# Arduino_shield.net
KiCad netlist of a schematic drawn in EAGLE
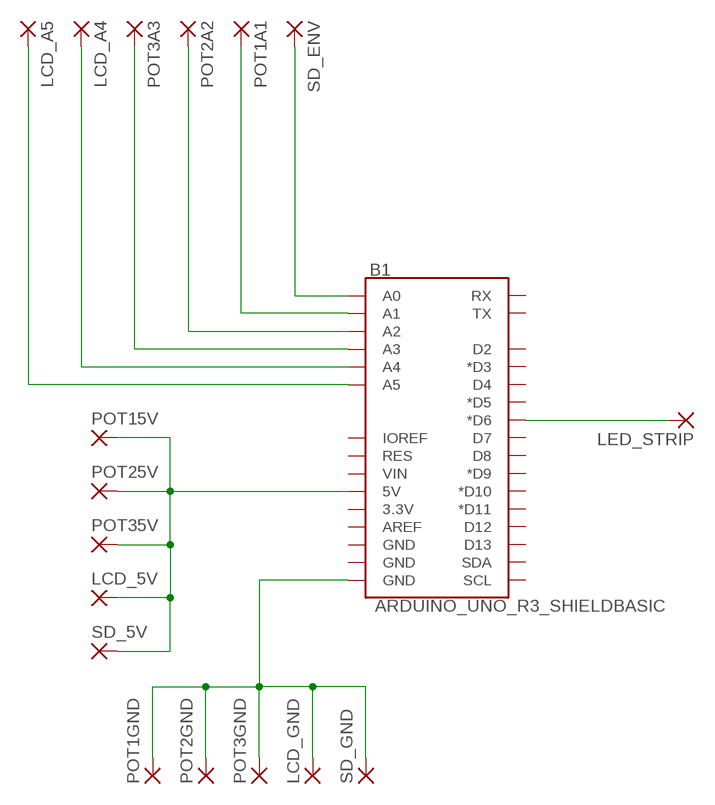
[diagram p0: schematic, sheet 1]

(export (version "E")
  (design (tool "Eeschema 10.0.6"))
  (components
    (comp (ref "B1")
      (value "ARDUINO_UNO_R3_SHIELDBASIC")
      (footprint "eagle-import:UNO_R3_SHIELD")
      (libsource (lib "eagle-import") (part "ARDUINO_UNO_R3_SHIELDBASIC"))
    )
    (comp (ref "LCD_5V")
      (value "1,6/0,9")
      (footprint "eagle-import:1,6_0,9")
      (libsource (lib "eagle-import") (part "1,6/0,9"))
    )
    (comp (ref "LCD_A4")
      (value "1,6/0,9")
      (footprint "eagle-import:1,6_0,9")
      (libsource (lib "eagle-import") (part "1,6/0,9"))
    )
    (comp (ref "LCD_A5")
      (value "1,6/0,9")
      (footprint "eagle-import:1,6_0,9")
      (libsource (lib "eagle-import") (part "1,6/0,9"))
    )
    (comp (ref "LCD_GND")
      (value "1,6/0,9")
      (footprint "eagle-import:1,6_0,9")
      (libsource (lib "eagle-import") (part "1,6/0,9"))
    )
    (comp (ref "LED_STRIP")
      (value "1,6/0,9")
      (footprint "eagle-import:1,6_0,9")
      (libsource (lib "eagle-import") (part "1,6/0,9"))
    )
    (comp (ref "POT1A1")
      (value "1,6/0,9")
      (footprint "eagle-import:1,6_0,9")
      (libsource (lib "eagle-import") (part "1,6/0,9"))
    )
    (comp (ref "POT1GND")
      (value "1,6/0,9")
      (footprint "eagle-import:1,6_0,9")
      (libsource (lib "eagle-import") (part "1,6/0,9"))
    )
    (comp (ref "POT2A2")
      (value "1,6/0,9")
      (footprint "eagle-import:1,6_0,9")
      (libsource (lib "eagle-import") (part "1,6/0,9"))
    )
    (comp (ref "POT2GND")
      (value "1,6/0,9")
      (footprint "eagle-import:1,6_0,9")
      (libsource (lib "eagle-import") (part "1,6/0,9"))
    )
    (comp (ref "POT3A3")
      (value "1,6/0,9")
      (footprint "eagle-import:1,6_0,9")
      (libsource (lib "eagle-import") (part "1,6/0,9"))
    )
    (comp (ref "POT3GND")
      (value "1,6/0,9")
      (footprint "eagle-import:1,6_0,9")
      (libsource (lib "eagle-import") (part "1,6/0,9"))
    )
    (comp (ref "POT15V")
      (value "1,6/0,9")
      (footprint "eagle-import:1,6_0,9")
      (libsource (lib "eagle-import") (part "1,6/0,9"))
    )
    (comp (ref "POT25V")
      (value "1,6/0,9")
      (footprint "eagle-import:1,6_0,9")
      (libsource (lib "eagle-import") (part "1,6/0,9"))
    )
    (comp (ref "POT35V")
      (value "1,6/0,9")
      (footprint "eagle-import:1,6_0,9")
      (libsource (lib "eagle-import") (part "1,6/0,9"))
    )
    (comp (ref "SD_5V")
      (value "1,6/0,9")
      (footprint "eagle-import:1,6_0,9")
      (libsource (lib "eagle-import") (part "1,6/0,9"))
    )
    (comp (ref "SD_ENV")
      (value "1,6/0,9")
      (footprint "eagle-import:1,6_0,9")
      (libsource (lib "eagle-import") (part "1,6/0,9"))
    )
    (comp (ref "SD_GND")
      (value "1,6/0,9")
      (footprint "eagle-import:1,6_0,9")
      (libsource (lib "eagle-import") (part "1,6/0,9"))
    )
  )
  (nets
    (net (code "1") (name "Net-(B1-*D6)") (class "Default")
      (node (ref "B1") (pin "D6") (pinfunction "*D6_D6") (pintype "bidirectional"))
      (node (ref "LED_STRIP") (pin "1") (pinfunction "P_1") (pintype "passive"))
    )
    (net (code "2") (name "Net-(LCD_5V-P)") (class "Default")
      (node (ref "B1") (pin "5V") (pinfunction "5V_5V") (pintype "bidirectional"))
      (node (ref "LCD_5V") (pin "1") (pinfunction "P_1") (pintype "passive"))
      (node (ref "POT15V") (pin "1") (pinfunction "P_1") (pintype "passive"))
      (node (ref "POT25V") (pin "1") (pinfunction "P_1") (pintype "passive"))
      (node (ref "POT35V") (pin "1") (pinfunction "P_1") (pintype "passive"))
      (node (ref "SD_5V") (pin "1") (pinfunction "P_1") (pintype "passive"))
    )
    (net (code "3") (name "Net-(LCD_A4-P)") (class "Default")
      (node (ref "B1") (pin "A4") (pinfunction "A4_A4") (pintype "bidirectional"))
      (node (ref "LCD_A4") (pin "1") (pinfunction "P_1") (pintype "passive"))
    )
    (net (code "4") (name "Net-(LCD_A5-P)") (class "Default")
      (node (ref "B1") (pin "A5") (pinfunction "A5_A5") (pintype "bidirectional"))
      (node (ref "LCD_A5") (pin "1") (pinfunction "P_1") (pintype "passive"))
    )
    (net (code "5") (name "Net-(LCD_GND-P)") (class "Default")
      (node (ref "B1") (pin "GND@0") (pinfunction "GND_GND@0") (pintype "bidirectional"))
      (node (ref "LCD_GND") (pin "1") (pinfunction "P_1") (pintype "passive"))
      (node (ref "POT1GND") (pin "1") (pinfunction "P_1") (pintype "passive"))
      (node (ref "POT2GND") (pin "1") (pinfunction "P_1") (pintype "passive"))
      (node (ref "POT3GND") (pin "1") (pinfunction "P_1") (pintype "passive"))
      (node (ref "SD_GND") (pin "1") (pinfunction "P_1") (pintype "passive"))
    )
    (net (code "6") (name "Net-(POT1A1-P)") (class "Default")
      (node (ref "B1") (pin "A1") (pinfunction "A1_A1") (pintype "bidirectional"))
      (node (ref "POT1A1") (pin "1") (pinfunction "P_1") (pintype "passive"))
    )
    (net (code "7") (name "Net-(POT2A2-P)") (class "Default")
      (node (ref "B1") (pin "A2") (pinfunction "A2_A2") (pintype "bidirectional"))
      (node (ref "POT2A2") (pin "1") (pinfunction "P_1") (pintype "passive"))
    )
    (net (code "8") (name "Net-(POT3A3-P)") (class "Default")
      (node (ref "B1") (pin "A3") (pinfunction "A3_A3") (pintype "bidirectional"))
      (node (ref "POT3A3") (pin "1") (pinfunction "P_1") (pintype "passive"))
    )
    (net (code "9") (name "Net-(SD_ENV-P)") (class "Default")
      (node (ref "B1") (pin "A0") (pinfunction "A0_A0") (pintype "bidirectional"))
      (node (ref "SD_ENV") (pin "1") (pinfunction "P_1") (pintype "passive"))
    )
    (net (code "10") (name "unconnected-(B1-*D3-PadD3)") (class "Default")
      (node (ref "B1") (pin "D3") (pinfunction "*D3_D3") (pintype "bidirectional"))
    )
    (net (code "11") (name "unconnected-(B1-*D5-PadD5)") (class "Default")
      (node (ref "B1") (pin "D5") (pinfunction "*D5_D5") (pintype "bidirectional"))
    )
    (net (code "12") (name "unconnected-(B1-*D9-PadD9)") (class "Default")
      (node (ref "B1") (pin "D9") (pinfunction "*D9_D9") (pintype "bidirectional"))
    )
    (net (code "13") (name "unconnected-(B1-*D10-PadD10)") (class "Default")
      (node (ref "B1") (pin "D10") (pinfunction "*D10_D10") (pintype "bidirectional"))
    )
    (net (code "14") (name "unconnected-(B1-*D11-PadD11)") (class "Default")
      (node (ref "B1") (pin "D11") (pinfunction "*D11_D11") (pintype "bidirectional"))
    )
    (net (code "15") (name "unconnected-(B1-GND-PadGND@1)") (class "Default")
      (node (ref "B1") (pin "GND@1") (pinfunction "GND_GND@1") (pintype "bidirectional"))
    )
    (net (code "16") (name "unconnected-(B1-GND-PadGND@2)") (class "Default")
      (node (ref "B1") (pin "GND@2") (pinfunction "GND_GND@2") (pintype "bidirectional"))
    )
    (net (code "17") (name "unconnected-(B1-Pad3.3V)") (class "Default")
      (node (ref "B1") (pin "3.3V") (pinfunction "3.3V_3.3V") (pintype "bidirectional"))
    )
    (net (code "18") (name "unconnected-(B1-PadAREF)") (class "Default")
      (node (ref "B1") (pin "AREF") (pinfunction "AREF_AREF") (pintype "bidirectional"))
    )
    (net (code "19") (name "unconnected-(B1-PadD2)") (class "Default")
      (node (ref "B1") (pin "D2") (pinfunction "D2_D2") (pintype "bidirectional"))
    )
    (net (code "20") (name "unconnected-(B1-PadD4)") (class "Default")
      (node (ref "B1") (pin "D4") (pinfunction "D4_D4") (pintype "bidirectional"))
    )
    (net (code "21") (name "unconnected-(B1-PadD7)") (class "Default")
      (node (ref "B1") (pin "D7") (pinfunction "D7_D7") (pintype "bidirectional"))
    )
    (net (code "22") (name "unconnected-(B1-PadD8)") (class "Default")
      (node (ref "B1") (pin "D8") (pinfunction "D8_D8") (pintype "bidirectional"))
    )
    (net (code "23") (name "unconnected-(B1-PadD12)") (class "Default")
      (node (ref "B1") (pin "D12") (pinfunction "D12_D12") (pintype "bidirectional"))
    )
    (net (code "24") (name "unconnected-(B1-PadD13)") (class "Default")
      (node (ref "B1") (pin "D13") (pinfunction "D13_D13") (pintype "bidirectional"))
    )
    (net (code "25") (name "unconnected-(B1-PadIOREF)") (class "Default")
      (node (ref "B1") (pin "IOREF") (pinfunction "IOREF_IOREF") (pintype "bidirectional"))
    )
    (net (code "26") (name "unconnected-(B1-PadRES)") (class "Default")
      (node (ref "B1") (pin "RES") (pinfunction "RES_RES") (pintype "bidirectional"))
    )
    (net (code "27") (name "unconnected-(B1-PadRX)") (class "Default")
      (node (ref "B1") (pin "RX") (pinfunction "RX_RX") (pintype "bidirectional"))
    )
    (net (code "28") (name "unconnected-(B1-PadSCL)") (class "Default")
      (node (ref "B1") (pin "SCL") (pinfunction "SCL_SCL") (pintype "bidirectional"))
    )
    (net (code "29") (name "unconnected-(B1-PadSDA)") (class "Default")
      (node (ref "B1") (pin "SDA") (pinfunction "SDA_SDA") (pintype "bidirectional"))
    )
    (net (code "30") (name "unconnected-(B1-PadTX)") (class "Default")
      (node (ref "B1") (pin "TX") (pinfunction "TX_TX") (pintype "bidirectional"))
    )
    (net (code "31") (name "unconnected-(B1-PadVIN)") (class "Default")
      (node (ref "B1") (pin "VIN") (pinfunction "VIN_VIN") (pintype "bidirectional"))
    )
  )
)
